# Page11_PMIC_PCA9450B.net
KiCad netlist of a schematic drawn in Altium Designer
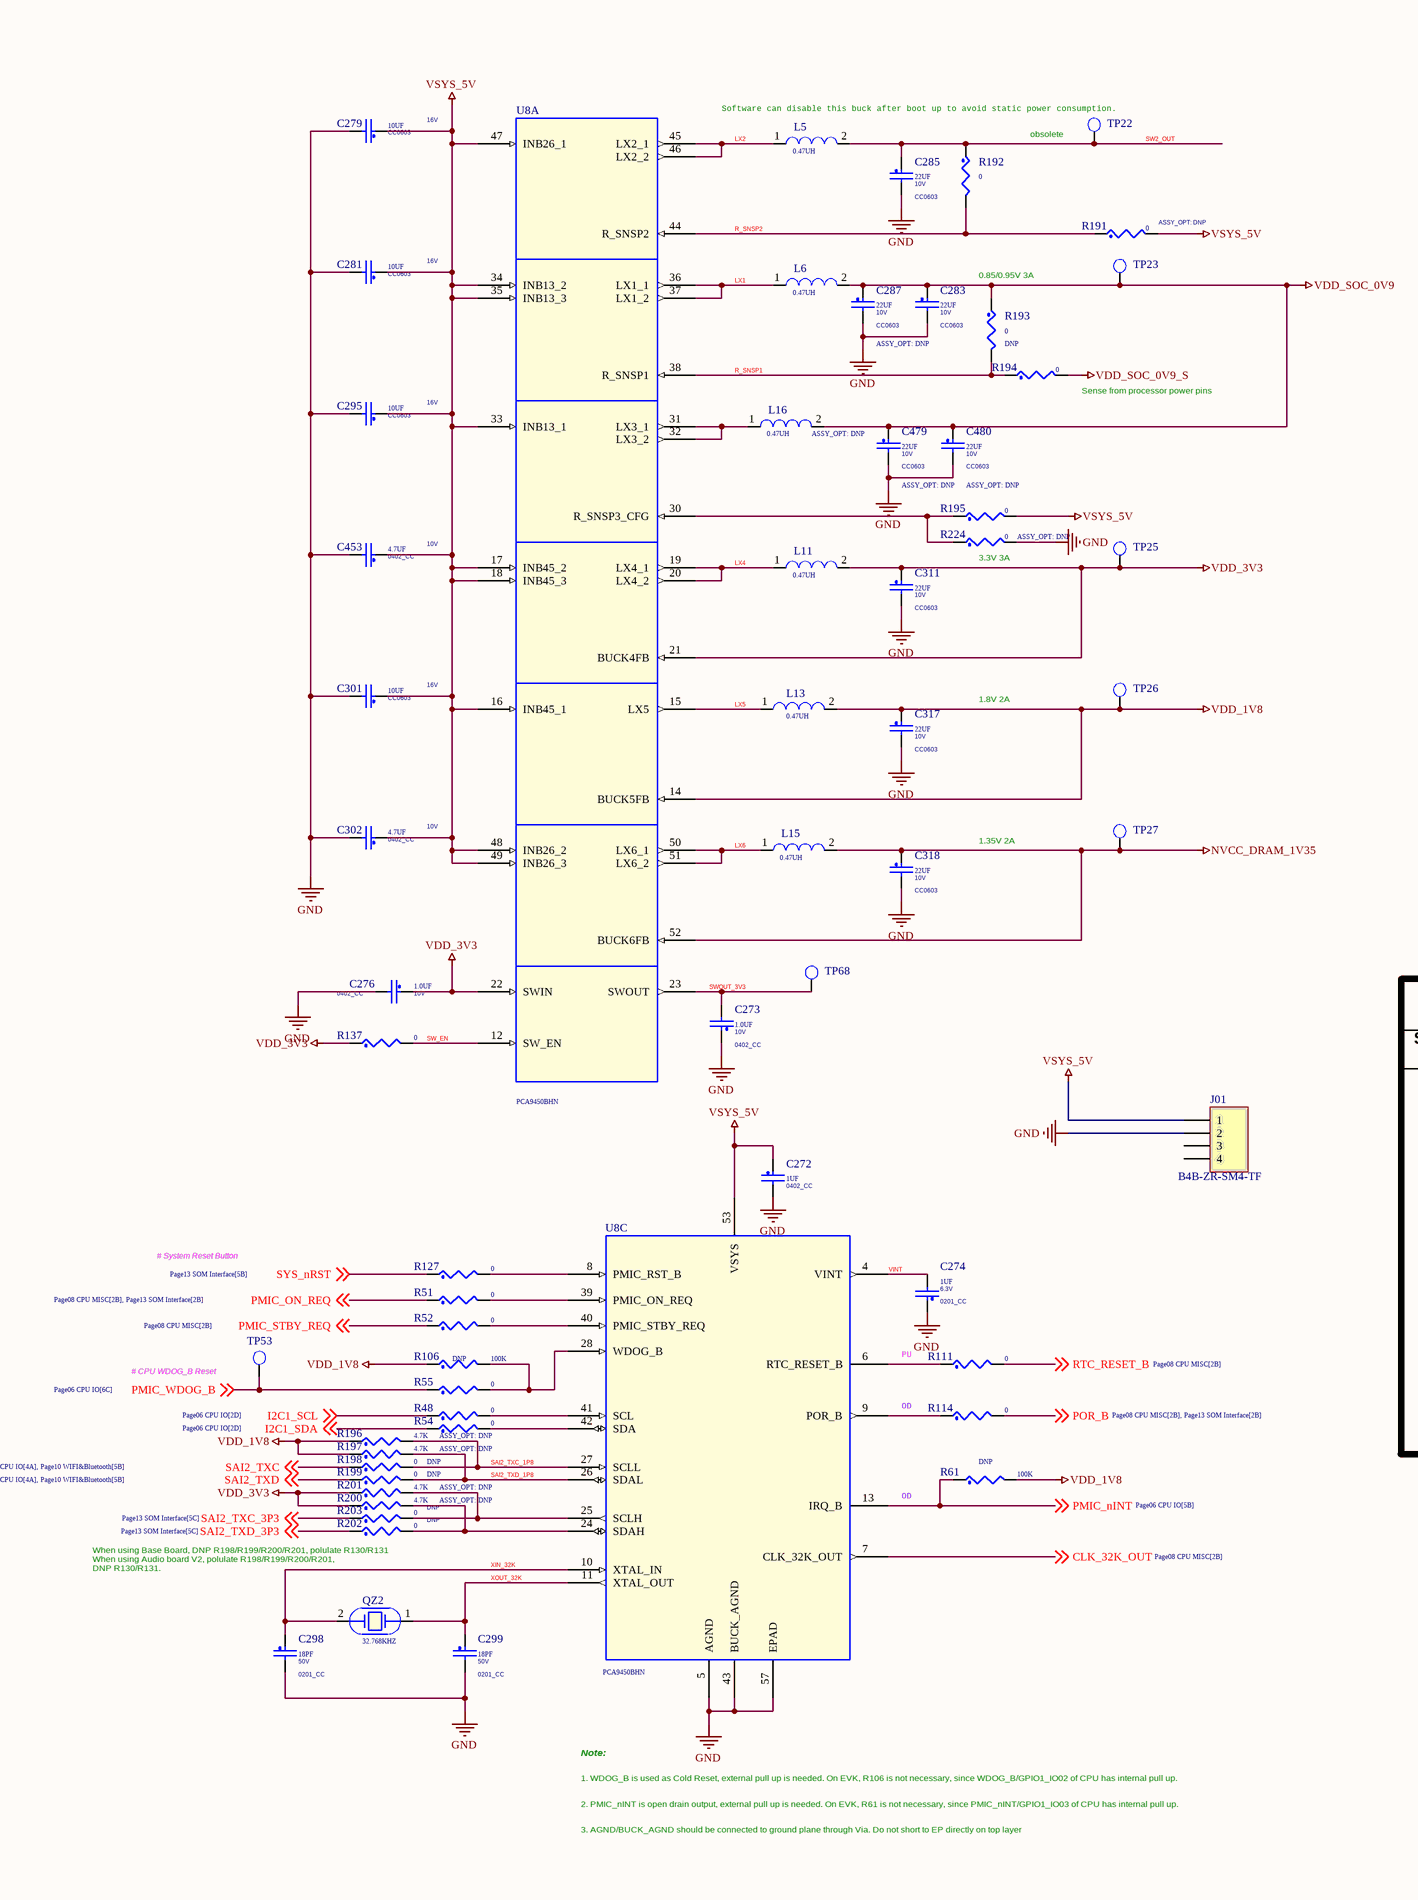
[diagram p0: Page11 PMIC PCA9450B.SchDoc, left]
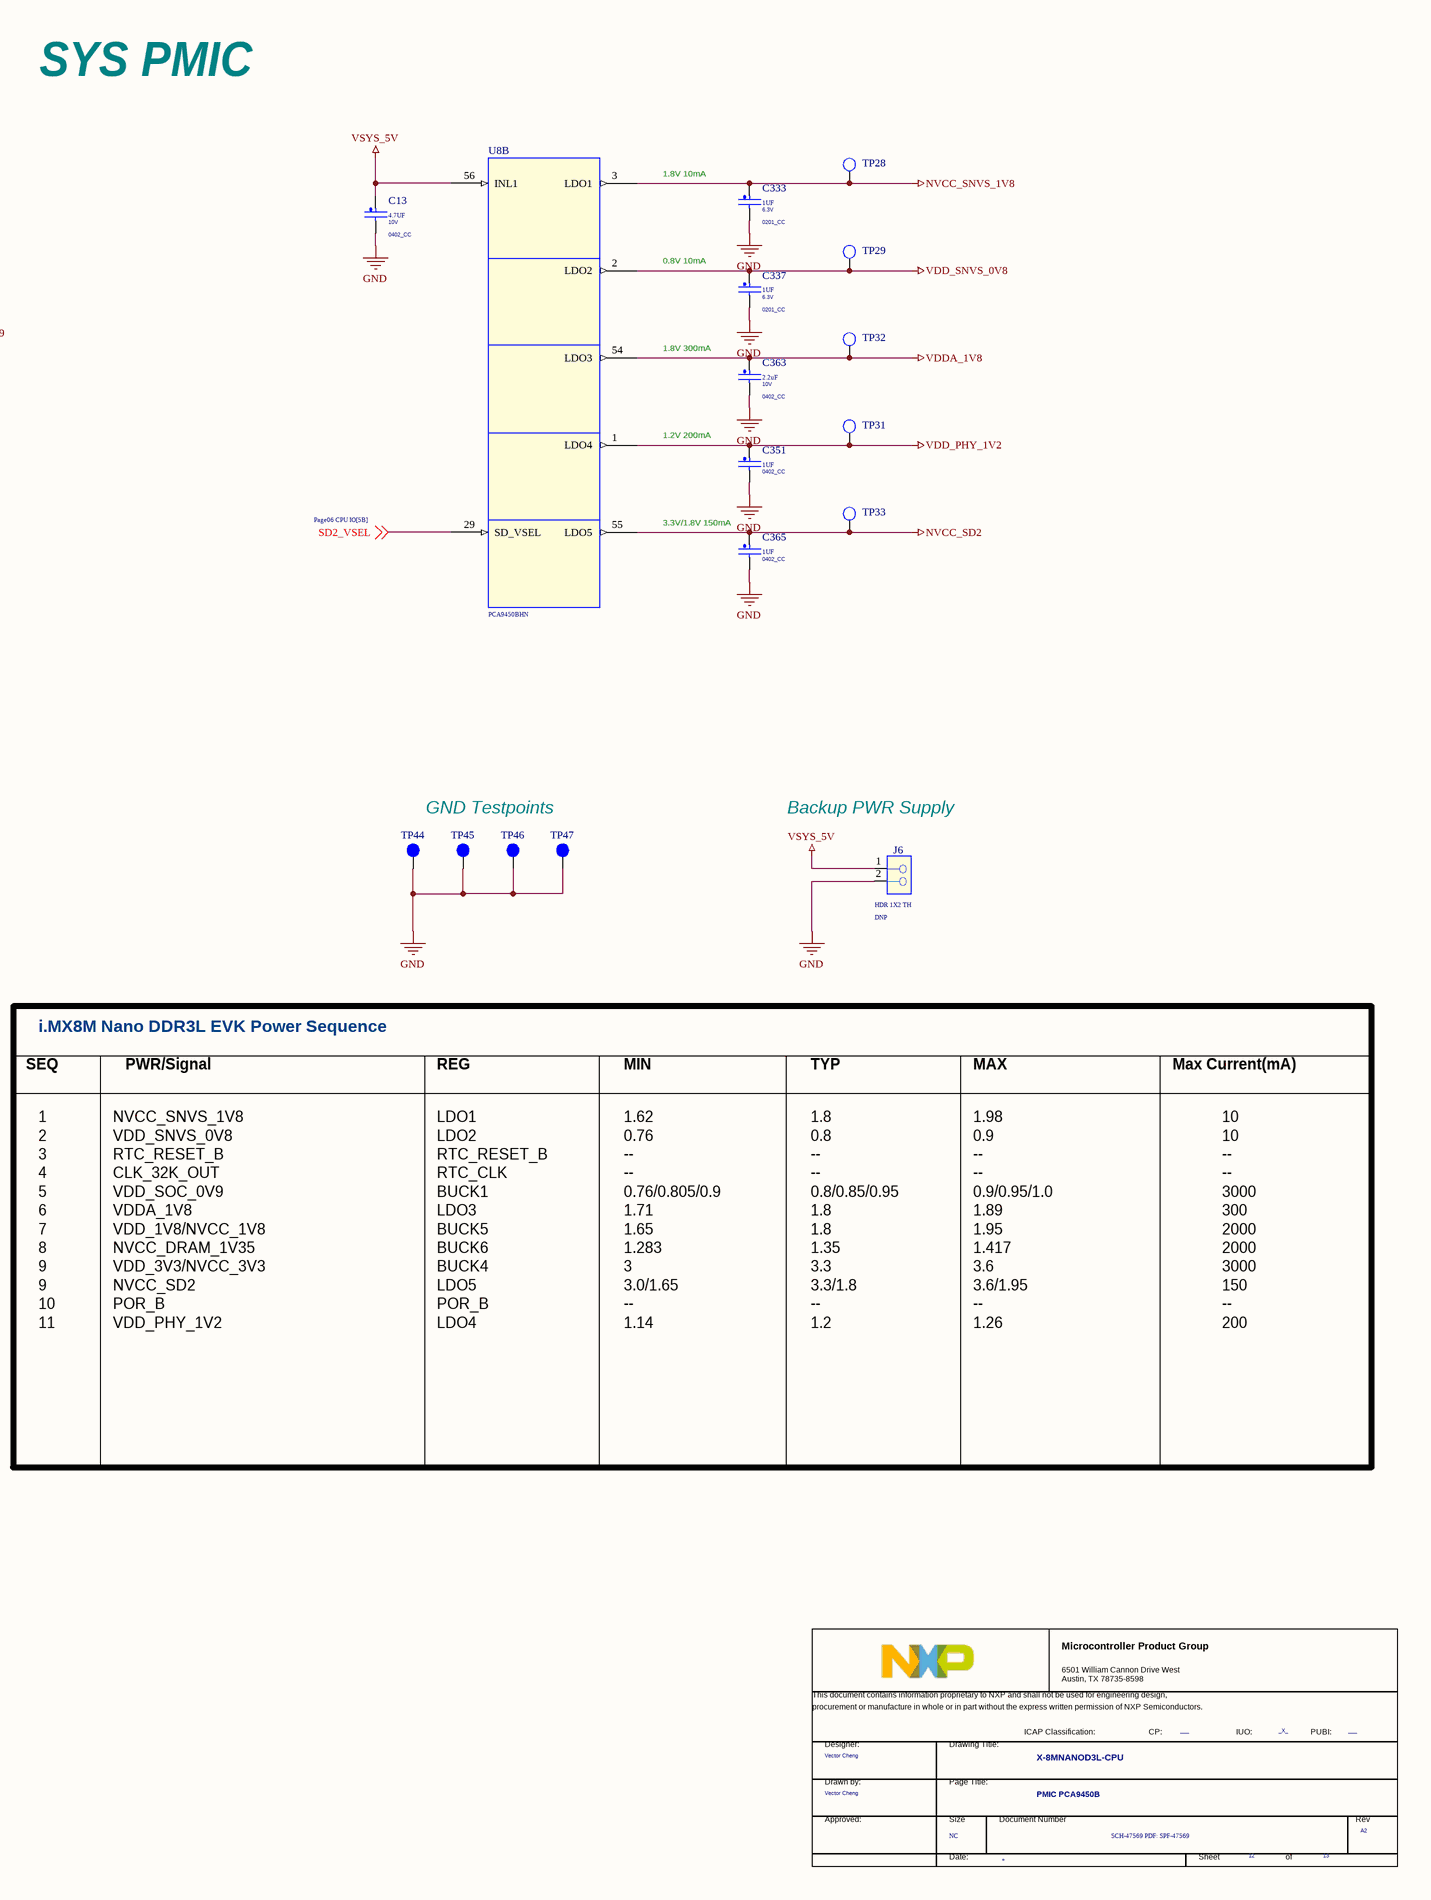
[diagram p1: Page11 PMIC PCA9450B.SchDoc, right]

(export (version "E")
  (design (tool "Eeschema 10.0.6"))
  (components
    (comp (ref "C13")
      (value "4.7UF")
      (footprint "0402_CC - C")
      (description "CAP CER 4.7uF 10V 10% X5R 0402")
      (fields
        (field (name "VOLTAGE") "10V")
        (field (name "TOLERANCE") "10%")
        (field (name "PCB FOOTPRINT") "0402_CC")
      )
      (libsource (lib "*") (part "CAP_NP"))
    )
    (comp (ref "C272")
      (value "1UF")
      (footprint "0402_CC - C")
      (description "CAP CER 1uF 10V 10% X7S 0402")
      (fields
        (field (name "VOLTAGE") "10")
        (field (name "TOLERANCE") "10%")
        (field (name "PCB FOOTPRINT") "0402_CC")
      )
      (libsource (lib "*") (part "CAP_NP"))
    )
    (comp (ref "C273")
      (value "1.0UF")
      (footprint "0402_CC - C")
      (description "CAP CER 1.0UF 10V 10% X5R 0402")
      (fields (field (name "PCB FOOTPRINT") "0402_CC") (field (name "VOLTAGE") "10V"))
      (libsource (lib "*") (part "CAP_NP"))
    )
    (comp (ref "C274")
      (value "1UF")
      (footprint "0201_CC - C")
      (description "CAP CER 1uF 6.3V 20% X5R 0201")
      (fields
        (field (name "TOLERANCE") "20%")
        (field (name "VOLTAGE") "6.3V")
        (field (name "PCB FOOTPRINT") "0201_CC")
      )
      (libsource (lib "*") (part "CAP_NP"))
    )
    (comp (ref "C276")
      (value "1.0UF")
      (footprint "0402_CC - C")
      (description "CAP CER 1.0UF 10V 10% X5R 0402")
      (fields (field (name "PCB FOOTPRINT") "0402_CC") (field (name "VOLTAGE") "10V"))
      (libsource (lib "*") (part "CAP_NP"))
    )
    (comp (ref "C279")
      (value "10UF")
      (footprint "0603_CC")
      (description "CAP CER 10.0uF 16V 10% X5R 0603")
      (fields
        (field (name "VOLTAGE") "16V")
        (field (name "TOLERANCE") "10%")
        (field (name "PCB FOOTPRINT") "CC0603")
      )
      (libsource (lib "*") (part "CAP_NP"))
    )
    (comp (ref "C281")
      (value "10UF")
      (footprint "0603_CC")
      (description "CAP CER 10.0uF 16V 10% X5R 0603")
      (fields
        (field (name "VOLTAGE") "16V")
        (field (name "TOLERANCE") "10%")
        (field (name "PCB FOOTPRINT") "CC0603")
      )
      (libsource (lib "*") (part "CAP_NP"))
    )
    (comp (ref "C283")
      (value "22UF")
      (footprint "0603_CC")
      (description "CAP CER 22uF 10V 20% X5R 0603")
      (fields
        (field (name "VOLTAGE") "10V")
        (field (name "TOLERANCE") "20%")
        (field (name "PCB FOOTPRINT") "CC0603")
      )
      (libsource (lib "*") (part "CAP_NP"))
    )
    (comp (ref "C285")
      (value "22UF")
      (footprint "0603_CC")
      (description "CAP CER 22uF 10V 20% X5R 0603")
      (fields
        (field (name "PCB FOOTPRINT") "CC0603")
        (field (name "VOLTAGE") "10V")
        (field (name "TOLERANCE") "20%")
      )
      (libsource (lib "*") (part "CAP_NP"))
    )
    (comp (ref "C287")
      (value "22UF")
      (footprint "0603_CC")
      (description "CAP CER 22uF 10V 20% X5R 0603")
      (fields
        (field (name "ASSY_OPT") "DNP")
        (field (name "VOLTAGE") "10V")
        (field (name "TOLERANCE") "20%")
        (field (name "PCB FOOTPRINT") "CC0603")
      )
      (libsource (lib "*") (part "CAP_NP"))
    )
    (comp (ref "C295")
      (value "10UF")
      (footprint "0603_CC")
      (description "CAP CER 10.0uF 16V 10% X5R 0603")
      (fields
        (field (name "TOLERANCE") "10%")
        (field (name "VOLTAGE") "16V")
        (field (name "PCB FOOTPRINT") "CC0603")
      )
      (libsource (lib "*") (part "CAP_NP"))
    )
    (comp (ref "C298")
      (value "18PF")
      (footprint "0201_CC - C")
      (description "CAP CER 18pF 50V 5% C0G 0201")
      (fields
        (field (name "VOLTAGE") "50V")
        (field (name "TOLERANCE") "5%")
        (field (name "PCB FOOTPRINT") "0201_CC")
      )
      (libsource (lib "*") (part "CAP_NP"))
    )
    (comp (ref "C299")
      (value "18PF")
      (footprint "0201_CC - C")
      (description "CAP CER 18pF 50V 5% C0G 0201")
      (fields
        (field (name "TOLERANCE") "5%")
        (field (name "VOLTAGE") "50V")
        (field (name "PCB FOOTPRINT") "0201_CC")
      )
      (libsource (lib "*") (part "CAP_NP"))
    )
    (comp (ref "C301")
      (value "10UF")
      (footprint "0603_CC")
      (description "CAP CER 10.0uF 16V 10% X5R 0603")
      (fields
        (field (name "TOLERANCE") "10%")
        (field (name "VOLTAGE") "16V")
        (field (name "PCB FOOTPRINT") "CC0603")
      )
      (libsource (lib "*") (part "CAP_NP"))
    )
    (comp (ref "C302")
      (value "4.7UF")
      (footprint "0402_CC - C")
      (description "CAP CER 4.7uF 10V 10% X5R 0402")
      (fields
        (field (name "PCB FOOTPRINT") "0402_CC")
        (field (name "TOLERANCE") "10%")
        (field (name "VOLTAGE") "10V")
      )
      (libsource (lib "*") (part "CAP_NP"))
    )
    (comp (ref "C311")
      (value "22UF")
      (footprint "0603_CC")
      (description "CAP CER 22uF 10V 20% X5R 0603")
      (fields
        (field (name "VOLTAGE") "10V")
        (field (name "TOLERANCE") "20%")
        (field (name "PCB FOOTPRINT") "CC0603")
      )
      (libsource (lib "*") (part "CAP_NP"))
    )
    (comp (ref "C317")
      (value "22UF")
      (footprint "0603_CC")
      (description "CAP CER 22uF 10V 20% X5R 0603")
      (fields
        (field (name "VOLTAGE") "10V")
        (field (name "TOLERANCE") "20%")
        (field (name "PCB FOOTPRINT") "CC0603")
      )
      (libsource (lib "*") (part "CAP_NP"))
    )
    (comp (ref "C318")
      (value "22UF")
      (footprint "0603_CC")
      (description "CAP CER 22uF 10V 20% X5R 0603")
      (fields
        (field (name "VOLTAGE") "10V")
        (field (name "TOLERANCE") "20%")
        (field (name "PCB FOOTPRINT") "CC0603")
      )
      (libsource (lib "*") (part "CAP_NP"))
    )
    (comp (ref "C333")
      (value "1UF")
      (footprint "0201_CC - C")
      (description "CAP CER 1uF 6.3V 20% X5R 0201")
      (fields
        (field (name "VOLTAGE") "6.3V")
        (field (name "TOLERANCE") "20%")
        (field (name "PCB FOOTPRINT") "0201_CC")
      )
      (libsource (lib "*") (part "CAP_NP"))
    )
    (comp (ref "C337")
      (value "1UF")
      (footprint "0201_CC - C")
      (description "CAP CER 1uF 6.3V 20% X5R 0201")
      (fields
        (field (name "VOLTAGE") "6.3V")
        (field (name "TOLERANCE") "20%")
        (field (name "PCB FOOTPRINT") "0201_CC")
      )
      (libsource (lib "*") (part "CAP_NP"))
    )
    (comp (ref "C351")
      (value "1UF")
      (footprint "0402_CC - C")
      (description "CAP CER 1uF 10V 10% X7S 0402")
      (fields
        (field (name "TOLERANCE") "10%")
        (field (name "VOLTAGE") "10")
        (field (name "PCB FOOTPRINT") "0402_CC")
      )
      (libsource (lib "*") (part "CAP_NP"))
    )
    (comp (ref "C363")
      (value "2.2uF")
      (footprint "0402_CC - C")
      (description "CAP CER 2.2uF 10V 10% X5R 0402")
      (fields
        (field (name "TOLERANCE") "10%")
        (field (name "VOLTAGE") "10V")
        (field (name "PCB FOOTPRINT") "0402_CC")
      )
      (libsource (lib "*") (part "CAP_NP"))
    )
    (comp (ref "C365")
      (value "1UF")
      (footprint "0402_CC - C")
      (description "CAP CER 1uF 10V 10% X7S 0402")
      (fields
        (field (name "VOLTAGE") "10")
        (field (name "TOLERANCE") "10%")
        (field (name "PCB FOOTPRINT") "0402_CC")
      )
      (libsource (lib "*") (part "CAP_NP"))
    )
    (comp (ref "C453")
      (value "4.7UF")
      (footprint "0402_CC - C")
      (description "CAP CER 4.7uF 10V 10% X5R 0402")
      (fields
        (field (name "PCB FOOTPRINT") "0402_CC")
        (field (name "VOLTAGE") "10V")
        (field (name "TOLERANCE") "10%")
      )
      (libsource (lib "*") (part "CAP_NP"))
    )
    (comp (ref "C479")
      (value "22UF")
      (footprint "0603_CC")
      (description "CAP CER 22uF 10V 20% X5R 0603")
      (fields
        (field (name "ASSY_OPT") "DNP")
        (field (name "TOLERANCE") "20%")
        (field (name "VOLTAGE") "10V")
        (field (name "PCB FOOTPRINT") "CC0603")
      )
      (libsource (lib "*") (part "CAP_NP"))
    )
    (comp (ref "C480")
      (value "22UF")
      (footprint "0603_CC")
      (description "CAP CER 22uF 10V 20% X5R 0603")
      (fields
        (field (name "ASSY_OPT") "DNP")
        (field (name "TOLERANCE") "20%")
        (field (name "VOLTAGE") "10V")
        (field (name "PCB FOOTPRINT") "CC0603")
      )
      (libsource (lib "*") (part "CAP_NP"))
    )
    (comp (ref "J01")
      (value "B4B-ZR-SM4-TF")
      (footprint "JST_B4B-ZR-SM4-TFT(LF)(SN)")
      (fields (field (name "PUBLISHER") "Altium Limited"))
      (libsource (lib "Miscellaneous Connectors") (part "Header 4"))
    )
    (comp (ref "J6")
      (value "HDR 1X2 TH")
      (footprint "HDR_1X2")
      (description "HDR 1X2 TH 100MIL SP 339H AU 98L")
      (fields (field (name "ASSY_OPT") "DNP"))
      (libsource (lib "*") (part "CONN_HDR_2X1"))
    )
    (comp (ref "L5")
      (value "0.47UH")
      (footprint "ind_sph2520")
      (description "IND PWR 0.47uH@1MHZ 4.7A 20% SMT")
      (fields (field (name "TOLERANCE") "20%"))
      (libsource (lib "*") (part "INDUCTOR"))
    )
    (comp (ref "L6")
      (value "0.47UH")
      (footprint "ind_sph2520")
      (description "IND PWR 0.47uH@1MHZ 4.7A 20% SMT")
      (fields (field (name "TOLERANCE") "20%"))
      (libsource (lib "*") (part "INDUCTOR"))
    )
    (comp (ref "L11")
      (value "0.47UH")
      (footprint "ind_sph2520")
      (description "IND PWR 0.47uH@1MHZ 4.7A 20% SMT")
      (fields (field (name "TOLERANCE") "20%"))
      (libsource (lib "*") (part "INDUCTOR"))
    )
    (comp (ref "L13")
      (value "0.47UH")
      (footprint "IND_SPH2520")
      (description "IND WW 0.47uH@1MHz 3.4A 20% 2016")
      (fields (field (name "TOLERANCE") "20%") (field (name "VOLTAGE") "20V DC"))
      (libsource (lib "*") (part "INDUCTOR"))
    )
    (comp (ref "L15")
      (value "0.47UH")
      (footprint "ind_sph2520")
      (description "IND PWR 0.47uH@1MHZ 4.7A 20% SMT")
      (fields (field (name "TOLERANCE") "20%"))
      (libsource (lib "*") (part "INDUCTOR"))
    )
    (comp (ref "L16")
      (value "0.47UH")
      (footprint "ind_sph2520")
      (description "IND PWR 0.47uH@1MHZ 4.7A 20% SMT")
      (fields (field (name "ASSY_OPT") "DNP") (field (name "TOLERANCE") "20%"))
      (libsource (lib "*") (part "INDUCTOR"))
    )
    (comp (ref "QZ2")
      (value "32.768KHZ")
      (footprint "XTAL_ABS07-32.768KHZ-T - duplicate")
      (description "XTAL 32.768KHZ 12.5PF 20PPM 3.2X1.5MM SMT")
      (libsource (lib "*") (part "XTAL"))
    )
    (comp (ref "R48")
      (value "0")
      (footprint "0402_CC_RES")
      (description "RES MF ZERO OHM 1/16W 5% 0402")
      (fields (field (name "TOLERANCE") "5%") (field (name "VOLTAGE") "1/16W"))
      (libsource (lib "*") (part "RES"))
    )
    (comp (ref "R51")
      (value "0")
      (footprint "0402_CC_RES")
      (description "RES MF ZERO OHM 1/16W 5% 0402")
      (fields (field (name "TOLERANCE") "5%") (field (name "VOLTAGE") "1/16W"))
      (libsource (lib "*") (part "RES"))
    )
    (comp (ref "R52")
      (value "0")
      (footprint "0402_CC_RES")
      (description "RES MF ZERO OHM 1/16W 5% 0402")
      (fields (field (name "TOLERANCE") "5%") (field (name "VOLTAGE") "1/16W"))
      (libsource (lib "*") (part "RES"))
    )
    (comp (ref "R54")
      (value "0")
      (footprint "0402_CC_RES")
      (description "RES MF ZERO OHM 1/16W 5% 0402")
      (fields (field (name "TOLERANCE") "5%") (field (name "VOLTAGE") "1/16W"))
      (libsource (lib "*") (part "RES"))
    )
    (comp (ref "R55")
      (value "0")
      (footprint "0402_CC_RES")
      (description "RES MF ZERO OHM 1/16W 5% 0402")
      (fields (field (name "VOLTAGE") "1/16W") (field (name "TOLERANCE") "5%"))
      (libsource (lib "*") (part "RES"))
    )
    (comp (ref "R61")
      (value "100K")
      (footprint "0201_RES")
      (description "RES MF 100K 1/20W 1% 0201")
      (fields (field (name "ASSY_OPT") "DNP") (field (name "TOLERANCE") "1%"))
      (libsource (lib "*") (part "RES"))
    )
    (comp (ref "R106")
      (value "100K")
      (footprint "0201_RES")
      (description "RES MF 100K 1/20W 1% 0201")
      (fields (field (name "ASSY_OPT") "DNP") (field (name "TOLERANCE") "1%"))
      (libsource (lib "*") (part "RES"))
    )
    (comp (ref "R111")
      (value "0")
      (footprint "0402_CC_RES")
      (description "RES MF ZERO OHM 1/16W 5% 0402")
      (fields (field (name "TOLERANCE") "5%") (field (name "VOLTAGE") "1/16W"))
      (libsource (lib "*") (part "RES"))
    )
    (comp (ref "R114")
      (value "0")
      (footprint "0402_CC_RES")
      (description "RES MF ZERO OHM 1/16W 5% 0402")
      (fields (field (name "TOLERANCE") "5%") (field (name "VOLTAGE") "1/16W"))
      (libsource (lib "*") (part "RES"))
    )
    (comp (ref "R127")
      (value "0")
      (footprint "0402_CC_RES")
      (description "RES MF ZERO OHM 1/16W 5% 0402")
      (fields (field (name "VOLTAGE") "1/16W") (field (name "TOLERANCE") "5%"))
      (libsource (lib "*") (part "RES"))
    )
    (comp (ref "R137")
      (value "0")
      (footprint "0402_CC_RES")
      (description "RES MF ZERO OHM 1/16W 5% 0402")
      (fields (field (name "TOLERANCE") "5%") (field (name "VOLTAGE") "1/16W"))
      (libsource (lib "*") (part "RES"))
    )
    (comp (ref "R191")
      (value "0")
      (footprint "0402_CC_RES")
      (description "RES MF ZERO OHM 1/16W 5% 0402")
      (fields
        (field (name "ASSY_OPT") "DNP")
        (field (name "TOLERANCE") "5%")
        (field (name "VOLTAGE") "1/16W")
      )
      (libsource (lib "*") (part "RES"))
    )
    (comp (ref "R192")
      (value "0")
      (footprint "0402_CC_RES")
      (description "RES MF ZERO OHM 1/16W 5% 0402")
      (fields (field (name "TOLERANCE") "5%") (field (name "VOLTAGE") "1/16W"))
      (libsource (lib "*") (part "RES"))
    )
    (comp (ref "R193")
      (value "0")
      (footprint "0402_CC_RES")
      (description "RES MF ZERO OHM 1/16W 5% 0402")
      (fields
        (field (name "ASSY_OPT") "DNP")
        (field (name "TOLERANCE") "5%")
        (field (name "VOLTAGE") "1/16W")
      )
      (libsource (lib "*") (part "RES"))
    )
    (comp (ref "R194")
      (value "0")
      (footprint "0402_CC_RES")
      (description "RES MF ZERO OHM 1/16W 5% 0402")
      (fields (field (name "TOLERANCE") "5%") (field (name "VOLTAGE") "1/16W"))
      (libsource (lib "*") (part "RES"))
    )
    (comp (ref "R195")
      (value "0")
      (footprint "0402_CC_RES")
      (description "RES MF ZERO OHM 1/16W 5% 0402")
      (fields (field (name "TOLERANCE") "5%") (field (name "VOLTAGE") "1/16W"))
      (libsource (lib "*") (part "RES"))
    )
    (comp (ref "R196")
      (value "4.7K")
      (footprint "0201_RES")
      (description "RES MF 4.7K 1/20W 5% AEC-Q200 0201")
      (fields (field (name "ASSY_OPT") "DNP") (field (name "TOLERANCE") "5%"))
      (libsource (lib "*") (part "RES"))
    )
    (comp (ref "R197")
      (value "4.7K")
      (footprint "0201_RES")
      (description "RES MF 4.7K 1/20W 5% AEC-Q200 0201")
      (fields (field (name "ASSY_OPT") "DNP") (field (name "TOLERANCE") "5%"))
      (libsource (lib "*") (part "RES"))
    )
    (comp (ref "R198")
      (value "0")
      (footprint "0402_CC_RES")
      (description "RES MF ZERO OHM 1/16W 5% 0402")
      (fields
        (field (name "ASSY_OPT") "DNP")
        (field (name "TOLERANCE") "5%")
        (field (name "VOLTAGE") "1/16W")
      )
      (libsource (lib "*") (part "RES"))
    )
    (comp (ref "R199")
      (value "0")
      (footprint "0402_CC_RES")
      (description "RES MF ZERO OHM 1/16W 5% 0402")
      (fields
        (field (name "ASSY_OPT") "DNP")
        (field (name "TOLERANCE") "5%")
        (field (name "VOLTAGE") "1/16W")
      )
      (libsource (lib "*") (part "RES"))
    )
    (comp (ref "R200")
      (value "4.7K")
      (footprint "0201_RES")
      (description "RES MF 4.7K 1/20W 5% AEC-Q200 0201")
      (fields (field (name "ASSY_OPT") "DNP") (field (name "TOLERANCE") "5%"))
      (libsource (lib "*") (part "RES"))
    )
    (comp (ref "R201")
      (value "4.7K")
      (footprint "0201_RES")
      (description "RES MF 4.7K 1/20W 5% AEC-Q200 0201")
      (fields (field (name "ASSY_OPT") "DNP") (field (name "TOLERANCE") "5%"))
      (libsource (lib "*") (part "RES"))
    )
    (comp (ref "R202")
      (value "0")
      (footprint "0402_CC_RES")
      (description "RES MF ZERO OHM 1/16W 5% 0402")
      (fields
        (field (name "ASSY_OPT") "DNP")
        (field (name "TOLERANCE") "5%")
        (field (name "VOLTAGE") "1/16W")
      )
      (libsource (lib "*") (part "RES"))
    )
    (comp (ref "R203")
      (value "0")
      (footprint "0402_CC_RES")
      (description "RES MF ZERO OHM 1/16W 5% 0402")
      (fields
        (field (name "ASSY_OPT") "DNP")
        (field (name "TOLERANCE") "5%")
        (field (name "VOLTAGE") "1/16W")
      )
      (libsource (lib "*") (part "RES"))
    )
    (comp (ref "R224")
      (value "0")
      (footprint "0402_CC_RES")
      (description "RES MF ZERO OHM 1/16W 5% 0402")
      (fields
        (field (name "ASSY_OPT") "DNP")
        (field (name "TOLERANCE") "5%")
        (field (name "VOLTAGE") "1/16W")
      )
      (libsource (lib "*") (part "RES"))
    )
    (comp (ref "TP22")
      (value "TP_35MIL")
      (footprint "Test Pin")
      (description "TEST POINT PAD .035 SMT, no part to order")
      (libsource (lib "*") (part "T POINT R"))
    )
    (comp (ref "TP23")
      (value "TP_35MIL")
      (footprint "Test Pin")
      (description "TEST POINT PAD .035 SMT, no part to order")
      (libsource (lib "*") (part "T POINT R"))
    )
    (comp (ref "TP25")
      (value "TP_35MIL")
      (footprint "Test Pin")
      (description "TEST POINT PAD .035 SMT, no part to order")
      (libsource (lib "*") (part "T POINT R"))
    )
    (comp (ref "TP26")
      (value "TP_35MIL")
      (footprint "Test Pin")
      (description "TEST POINT PAD .035 SMT, no part to order")
      (libsource (lib "*") (part "T POINT R"))
    )
    (comp (ref "TP27")
      (value "TP_35MIL")
      (footprint "Test Pin")
      (description "TEST POINT PAD .035 SMT, no part to order")
      (libsource (lib "*") (part "T POINT R"))
    )
    (comp (ref "TP28")
      (value "TP_35MIL")
      (footprint "Test Pin")
      (description "TEST POINT PAD .035 SMT, no part to order")
      (libsource (lib "*") (part "T POINT R"))
    )
    (comp (ref "TP29")
      (value "TP_35MIL")
      (footprint "Test Pin")
      (description "TEST POINT PAD .035 SMT, no part to order")
      (libsource (lib "*") (part "T POINT R"))
    )
    (comp (ref "TP31")
      (value "TP_35MIL")
      (footprint "Test Pin")
      (description "TEST POINT PAD .035 SMT, no part to order")
      (libsource (lib "*") (part "T POINT R"))
    )
    (comp (ref "TP32")
      (value "TP_35MIL")
      (footprint "Test Pin")
      (description "TEST POINT PAD .035 SMT, no part to order")
      (libsource (lib "*") (part "T POINT R"))
    )
    (comp (ref "TP33")
      (value "TP_35MIL")
      (footprint "Test Pin")
      (description "TEST POINT PAD .035 SMT, no part to order")
      (libsource (lib "*") (part "T POINT R"))
    )
    (comp (ref "TP44")
      (value "TPAD_050")
      (footprint "Test Pin")
      (description "TEST POINT PAD 50MIL DIA SMT, NO PART TO ORDER")
      (libsource (lib "*") (part "TESTLOOP"))
    )
    (comp (ref "TP45")
      (value "TPAD_050")
      (footprint "Test Pin")
      (description "TEST POINT PAD 50MIL DIA SMT, NO PART TO ORDER")
      (libsource (lib "*") (part "TESTLOOP"))
    )
    (comp (ref "TP46")
      (value "TPAD_050")
      (footprint "Test Pin")
      (description "TEST POINT PAD 50MIL DIA SMT, NO PART TO ORDER")
      (libsource (lib "*") (part "TESTLOOP"))
    )
    (comp (ref "TP47")
      (value "TPAD_050")
      (footprint "Test Pin")
      (description "TEST POINT PAD 50MIL DIA SMT, NO PART TO ORDER")
      (libsource (lib "*") (part "TESTLOOP"))
    )
    (comp (ref "TP53")
      (value "TP_35MIL")
      (footprint "Test Pin")
      (description "TEST POINT PAD .035 SMT, no part to order")
      (libsource (lib "*") (part "T POINT R"))
    )
    (comp (ref "TP68")
      (value "TP_35MIL")
      (footprint "Test Pin")
      (description "TEST POINT PAD .035 SMT, no part to order")
      (libsource (lib "*") (part "T POINT R"))
    )
    (comp (ref "U8")
      (value "PCA9450BHN")
      (footprint "QFN40P700X700X100-57N-D")
      (description "IC POWER MANAGEMENT 2.7-5.5V HVQFN56")
      (fields (field (name "VOLTAGE") "2.7-5.5V"))
      (libsource (lib "*") (part "PCA9450_HVQFN56P_A"))
    )
  )
  (nets
    (net (code "1") (name "/LX1") (class "Default")
      (node (ref "L6") (pin "1") (pinfunction "1_1") (pintype "passive"))
      (node (ref "U8") (pin "36") (pinfunction "LX1_1_36") (pintype "output"))
      (node (ref "U8") (pin "37") (pinfunction "LX1_2_37") (pintype "output"))
    )
    (net (code "2") (name "/LX2") (class "Default")
      (node (ref "L5") (pin "1") (pinfunction "1_1") (pintype "passive"))
      (node (ref "U8") (pin "45") (pinfunction "LX2_1_45") (pintype "output"))
      (node (ref "U8") (pin "46") (pinfunction "LX2_2_46") (pintype "output"))
    )
    (net (code "3") (name "/LX4") (class "Default")
      (node (ref "L11") (pin "1") (pinfunction "1_1") (pintype "passive"))
      (node (ref "U8") (pin "19") (pinfunction "LX4_1_19") (pintype "output"))
      (node (ref "U8") (pin "20") (pinfunction "LX4_2_20") (pintype "output"))
    )
    (net (code "4") (name "/LX5") (class "Default")
      (node (ref "L13") (pin "1") (pinfunction "1_1") (pintype "passive"))
      (node (ref "U8") (pin "15") (pinfunction "LX5_15") (pintype "output"))
    )
    (net (code "5") (name "/LX6") (class "Default")
      (node (ref "L15") (pin "1") (pinfunction "1_1") (pintype "passive"))
      (node (ref "U8") (pin "50") (pinfunction "LX6_1_50") (pintype "output"))
      (node (ref "U8") (pin "51") (pinfunction "LX6_2_51") (pintype "output"))
    )
    (net (code "6") (name "/R_SNSP1") (class "Default")
      (node (ref "R193") (pin "2") (pinfunction "2_2") (pintype "passive"))
      (node (ref "R194") (pin "1") (pinfunction "1_1") (pintype "passive"))
      (node (ref "U8") (pin "38") (pinfunction "R_SNSP1_38") (pintype "input"))
    )
    (net (code "7") (name "/R_SNSP2") (class "Default")
      (node (ref "R191") (pin "1") (pinfunction "1_1") (pintype "passive"))
      (node (ref "R192") (pin "2") (pinfunction "2_2") (pintype "passive"))
      (node (ref "U8") (pin "44") (pinfunction "R_SNSP2_44") (pintype "input"))
    )
    (net (code "8") (name "/SAI2_TXC_1P8") (class "Default")
      (node (ref "R196") (pin "2") (pinfunction "2_2") (pintype "passive"))
      (node (ref "R198") (pin "2") (pinfunction "2_2") (pintype "passive"))
      (node (ref "U8") (pin "27") (pinfunction "SCLL_27") (pintype "input"))
    )
    (net (code "9") (name "/SAI2_TXD_1P8") (class "Default")
      (node (ref "R197") (pin "2") (pinfunction "2_2") (pintype "passive"))
      (node (ref "R199") (pin "2") (pinfunction "2_2") (pintype "passive"))
      (node (ref "U8") (pin "26") (pinfunction "SDAL_26") (pintype "bidirectional"))
    )
    (net (code "10") (name "/SW2_OUT") (class "Default")
      (node (ref "C285") (pin "1") (pinfunction "1_1") (pintype "passive"))
      (node (ref "L5") (pin "2") (pinfunction "2_2") (pintype "passive"))
      (node (ref "R192") (pin "1") (pinfunction "1_1") (pintype "passive"))
      (node (ref "TP22") (pin "1") (pinfunction "TP_1") (pintype "passive"))
    )
    (net (code "11") (name "/SWOUT_3V3") (class "Default")
      (node (ref "C273") (pin "2") (pinfunction "2_2") (pintype "passive"))
      (node (ref "TP68") (pin "1") (pinfunction "TP_1") (pintype "passive"))
      (node (ref "U8") (pin "23") (pinfunction "SWOUT_23") (pintype "output"))
    )
    (net (code "12") (name "/SW_EN") (class "Default")
      (node (ref "R137") (pin "2") (pinfunction "2_2") (pintype "passive"))
      (node (ref "U8") (pin "12") (pinfunction "SW_EN_12") (pintype "input"))
    )
    (net (code "13") (name "/VINT") (class "Default")
      (node (ref "C274") (pin "2") (pinfunction "2_2") (pintype "passive"))
      (node (ref "U8") (pin "4") (pinfunction "VINT_4") (pintype "output"))
    )
    (net (code "14") (name "/XIN_32K") (class "Default")
      (node (ref "C298") (pin "1") (pinfunction "1_1") (pintype "passive"))
      (node (ref "QZ2") (pin "2") (pinfunction "2_2") (pintype "passive"))
      (node (ref "U8") (pin "10") (pinfunction "XTAL_IN_10") (pintype "input"))
    )
    (net (code "15") (name "/XOUT_32K") (class "Default")
      (node (ref "C299") (pin "1") (pinfunction "1_1") (pintype "passive"))
      (node (ref "QZ2") (pin "1") (pinfunction "1_1") (pintype "passive"))
      (node (ref "U8") (pin "11") (pinfunction "XTAL_OUT_11") (pintype "output"))
    )
    (net (code "16") (name "CLK_32K_OUT") (class "Default")
      (node (ref "U8") (pin "7") (pinfunction "CLK_32K_OUT_7") (pintype "output"))
    )
    (net (code "17") (name "GND") (class "Default")
      (node (ref "C13") (pin "2") (pinfunction "2_2") (pintype "passive"))
      (node (ref "C272") (pin "2") (pinfunction "2_2") (pintype "passive"))
      (node (ref "C273") (pin "1") (pinfunction "1_1") (pintype "passive"))
      (node (ref "C274") (pin "1") (pinfunction "1_1") (pintype "passive"))
      (node (ref "C276") (pin "2") (pinfunction "2_2") (pintype "passive"))
      (node (ref "C279") (pin "2") (pinfunction "2_2") (pintype "passive"))
      (node (ref "C281") (pin "2") (pinfunction "2_2") (pintype "passive"))
      (node (ref "C283") (pin "2") (pinfunction "2_2") (pintype "passive"))
      (node (ref "C285") (pin "2") (pinfunction "2_2") (pintype "passive"))
      (node (ref "C287") (pin "2") (pinfunction "2_2") (pintype "passive"))
      (node (ref "C295") (pin "2") (pinfunction "2_2") (pintype "passive"))
      (node (ref "C298") (pin "2") (pinfunction "2_2") (pintype "passive"))
      (node (ref "C299") (pin "2") (pinfunction "2_2") (pintype "passive"))
      (node (ref "C301") (pin "2") (pinfunction "2_2") (pintype "passive"))
      (node (ref "C302") (pin "2") (pinfunction "2_2") (pintype "passive"))
      (node (ref "C311") (pin "2") (pinfunction "2_2") (pintype "passive"))
      (node (ref "C317") (pin "2") (pinfunction "2_2") (pintype "passive"))
      (node (ref "C318") (pin "2") (pinfunction "2_2") (pintype "passive"))
      (node (ref "C333") (pin "2") (pinfunction "2_2") (pintype "passive"))
      (node (ref "C337") (pin "2") (pinfunction "2_2") (pintype "passive"))
      (node (ref "C351") (pin "2") (pinfunction "2_2") (pintype "passive"))
      (node (ref "C363") (pin "2") (pinfunction "2_2") (pintype "passive"))
      (node (ref "C365") (pin "2") (pinfunction "2_2") (pintype "passive"))
      (node (ref "C453") (pin "2") (pinfunction "2_2") (pintype "passive"))
      (node (ref "C479") (pin "2") (pinfunction "2_2") (pintype "passive"))
      (node (ref "C480") (pin "2") (pinfunction "2_2") (pintype "passive"))
      (node (ref "J01") (pin "2") (pinfunction "2_2") (pintype "passive"))
      (node (ref "J6") (pin "2") (pinfunction "2_2") (pintype "passive"))
      (node (ref "R224") (pin "2") (pinfunction "2_2") (pintype "passive"))
      (node (ref "TP44") (pin "1") (pinfunction "Pin1_1") (pintype "passive"))
      (node (ref "TP45") (pin "1") (pinfunction "Pin1_1") (pintype "passive"))
      (node (ref "TP46") (pin "1") (pinfunction "Pin1_1") (pintype "passive"))
      (node (ref "TP47") (pin "1") (pinfunction "Pin1_1") (pintype "passive"))
      (node (ref "U8") (pin "43") (pinfunction "BUCK_AGND_43") (pintype "power_in"))
      (node (ref "U8") (pin "5") (pinfunction "AGND_5") (pintype "power_in"))
      (node (ref "U8") (pin "57") (pinfunction "EPAD_57") (pintype "power_in"))
    )
    (net (code "18") (name "I2C1_SCL") (class "Default")
      (node (ref "R48") (pin "1") (pinfunction "1_1") (pintype "passive"))
    )
    (net (code "19") (name "I2C1_SDA") (class "Default")
      (node (ref "R54") (pin "1") (pinfunction "1_1") (pintype "passive"))
    )
    (net (code "20") (name "NVCC_DRAM_1V35") (class "Default")
      (node (ref "C318") (pin "1") (pinfunction "1_1") (pintype "passive"))
      (node (ref "L15") (pin "2") (pinfunction "2_2") (pintype "passive"))
      (node (ref "TP27") (pin "1") (pinfunction "TP_1") (pintype "passive"))
      (node (ref "U8") (pin "52") (pinfunction "BUCK6FB_52") (pintype "input"))
    )
    (net (code "21") (name "NVCC_SD2") (class "Default")
      (node (ref "C365") (pin "1") (pinfunction "1_1") (pintype "passive"))
      (node (ref "TP33") (pin "1") (pinfunction "TP_1") (pintype "passive"))
      (node (ref "U8") (pin "55") (pinfunction "LDO5_55") (pintype "output"))
    )
    (net (code "22") (name "NVCC_SNVS_1V8") (class "Default")
      (node (ref "C333") (pin "1") (pinfunction "1_1") (pintype "passive"))
      (node (ref "TP28") (pin "1") (pinfunction "TP_1") (pintype "passive"))
      (node (ref "U8") (pin "3") (pinfunction "LDO1_3") (pintype "output"))
    )
    (net (code "23") (name "Net-(U8A-LX3_1)") (class "Default")
      (node (ref "L16") (pin "1") (pinfunction "1_1") (pintype "passive"))
      (node (ref "U8") (pin "31") (pinfunction "LX3_1_31") (pintype "output"))
      (node (ref "U8") (pin "32") (pinfunction "LX3_2_32") (pintype "output"))
    )
    (net (code "24") (name "Net-(U8A-R_SNSP3_CFG)") (class "Default")
      (node (ref "R195") (pin "1") (pinfunction "1_1") (pintype "passive"))
      (node (ref "R224") (pin "1") (pinfunction "1_1") (pintype "passive"))
      (node (ref "U8") (pin "30") (pinfunction "R_SNSP3_CFG_30") (pintype "input"))
    )
    (net (code "25") (name "Net-(U8C-PMIC_ON_REQ)") (class "Default")
      (node (ref "R51") (pin "2") (pinfunction "2_2") (pintype "passive"))
      (node (ref "U8") (pin "39") (pinfunction "PMIC_ON_REQ_39") (pintype "input"))
    )
    (net (code "26") (name "Net-(U8C-PMIC_RST_B)") (class "Default")
      (node (ref "R127") (pin "2") (pinfunction "2_2") (pintype "passive"))
      (node (ref "U8") (pin "8") (pinfunction "PMIC_RST_B_8") (pintype "input"))
    )
    (net (code "27") (name "Net-(U8C-PMIC_STBY_REQ)") (class "Default")
      (node (ref "R52") (pin "2") (pinfunction "2_2") (pintype "passive"))
      (node (ref "U8") (pin "40") (pinfunction "PMIC_STBY_REQ_40") (pintype "input"))
    )
    (net (code "28") (name "Net-(U8C-POR_B)") (class "Default")
      (node (ref "R114") (pin "1") (pinfunction "1_1") (pintype "passive"))
      (node (ref "U8") (pin "9") (pinfunction "POR_B_9") (pintype "output"))
    )
    (net (code "29") (name "Net-(U8C-RTC_RESET_B)") (class "Default")
      (node (ref "R111") (pin "1") (pinfunction "1_1") (pintype "passive"))
      (node (ref "U8") (pin "6") (pinfunction "RTC_RESET_B_6") (pintype "open_collector"))
    )
    (net (code "30") (name "Net-(U8C-SCL)") (class "Default")
      (node (ref "R48") (pin "2") (pinfunction "2_2") (pintype "passive"))
      (node (ref "U8") (pin "41") (pinfunction "SCL_41") (pintype "input"))
    )
    (net (code "31") (name "Net-(U8C-SCLH)") (class "Default")
      (node (ref "R201") (pin "2") (pinfunction "2_2") (pintype "passive"))
      (node (ref "R203") (pin "2") (pinfunction "2_2") (pintype "passive"))
      (node (ref "U8") (pin "25") (pinfunction "SCLH_25") (pintype "output"))
    )
    (net (code "32") (name "Net-(U8C-SDA)") (class "Default")
      (node (ref "R54") (pin "2") (pinfunction "2_2") (pintype "passive"))
      (node (ref "U8") (pin "42") (pinfunction "SDA_42") (pintype "bidirectional"))
    )
    (net (code "33") (name "Net-(U8C-SDAH)") (class "Default")
      (node (ref "R200") (pin "2") (pinfunction "2_2") (pintype "passive"))
      (node (ref "R202") (pin "2") (pinfunction "2_2") (pintype "passive"))
      (node (ref "U8") (pin "24") (pinfunction "SDAH_24") (pintype "bidirectional"))
    )
    (net (code "34") (name "Net-(U8C-WDOG_B)") (class "Default")
      (node (ref "R106") (pin "2") (pinfunction "2_2") (pintype "passive"))
      (node (ref "R55") (pin "2") (pinfunction "2_2") (pintype "passive"))
      (node (ref "U8") (pin "28") (pinfunction "WDOG_B_28") (pintype "input"))
    )
    (net (code "35") (name "PMIC_ON_REQ") (class "Default")
      (node (ref "R51") (pin "1") (pinfunction "1_1") (pintype "passive"))
    )
    (net (code "36") (name "PMIC_STBY_REQ") (class "Default")
      (node (ref "R52") (pin "1") (pinfunction "1_1") (pintype "passive"))
    )
    (net (code "37") (name "PMIC_WDOG_B") (class "Default")
      (node (ref "R55") (pin "1") (pinfunction "1_1") (pintype "passive"))
      (node (ref "TP53") (pin "1") (pinfunction "TP_1") (pintype "passive"))
    )
    (net (code "38") (name "PMIC_nINT") (class "Default")
      (node (ref "R61") (pin "1") (pinfunction "1_1") (pintype "passive"))
      (node (ref "U8") (pin "13") (pinfunction "IRQ_B_13") (pintype "open_collector"))
    )
    (net (code "39") (name "POR_B") (class "Default")
      (node (ref "R114") (pin "2") (pinfunction "2_2") (pintype "passive"))
    )
    (net (code "40") (name "RTC_RESET_B") (class "Default")
      (node (ref "R111") (pin "2") (pinfunction "2_2") (pintype "passive"))
    )
    (net (code "41") (name "SAI2_TXC") (class "Default")
      (node (ref "R198") (pin "1") (pinfunction "1_1") (pintype "passive"))
    )
    (net (code "42") (name "SAI2_TXC_3P3") (class "Default")
      (node (ref "R203") (pin "1") (pinfunction "1_1") (pintype "passive"))
    )
    (net (code "43") (name "SAI2_TXD") (class "Default")
      (node (ref "R199") (pin "1") (pinfunction "1_1") (pintype "passive"))
    )
    (net (code "44") (name "SAI2_TXD_3P3") (class "Default")
      (node (ref "R202") (pin "1") (pinfunction "1_1") (pintype "passive"))
    )
    (net (code "45") (name "SD2_VSEL") (class "Default")
      (node (ref "U8") (pin "29") (pinfunction "SD_VSEL_29") (pintype "input"))
    )
    (net (code "46") (name "SYS_nRST") (class "Default")
      (node (ref "R127") (pin "1") (pinfunction "1_1") (pintype "passive"))
    )
    (net (code "47") (name "VDDA_1V8") (class "Default")
      (node (ref "C363") (pin "1") (pinfunction "1_1") (pintype "passive"))
      (node (ref "TP32") (pin "1") (pinfunction "TP_1") (pintype "passive"))
      (node (ref "U8") (pin "54") (pinfunction "LDO3_54") (pintype "output"))
    )
    (net (code "48") (name "VDD_1V8") (class "Default")
      (node (ref "C317") (pin "1") (pinfunction "1_1") (pintype "passive"))
      (node (ref "L13") (pin "2") (pinfunction "2_2") (pintype "passive"))
      (node (ref "R106") (pin "1") (pinfunction "1_1") (pintype "passive"))
      (node (ref "R196") (pin "1") (pinfunction "1_1") (pintype "passive"))
      (node (ref "R197") (pin "1") (pinfunction "1_1") (pintype "passive"))
      (node (ref "R61") (pin "2") (pinfunction "2_2") (pintype "passive"))
      (node (ref "TP26") (pin "1") (pinfunction "TP_1") (pintype "passive"))
      (node (ref "U8") (pin "14") (pinfunction "BUCK5FB_14") (pintype "input"))
    )
    (net (code "49") (name "VDD_3V3") (class "Default")
      (node (ref "C276") (pin "1") (pinfunction "1_1") (pintype "passive"))
      (node (ref "C311") (pin "1") (pinfunction "1_1") (pintype "passive"))
      (node (ref "L11") (pin "2") (pinfunction "2_2") (pintype "passive"))
      (node (ref "R137") (pin "1") (pinfunction "1_1") (pintype "passive"))
      (node (ref "R200") (pin "1") (pinfunction "1_1") (pintype "passive"))
      (node (ref "R201") (pin "1") (pinfunction "1_1") (pintype "passive"))
      (node (ref "TP25") (pin "1") (pinfunction "TP_1") (pintype "passive"))
      (node (ref "U8") (pin "21") (pinfunction "BUCK4FB_21") (pintype "input"))
      (node (ref "U8") (pin "22") (pinfunction "SWIN_22") (pintype "input"))
    )
    (net (code "50") (name "VDD_PHY_1V2") (class "Default")
      (node (ref "C351") (pin "1") (pinfunction "1_1") (pintype "passive"))
      (node (ref "TP31") (pin "1") (pinfunction "TP_1") (pintype "passive"))
      (node (ref "U8") (pin "1") (pinfunction "LDO4_1") (pintype "output"))
    )
    (net (code "51") (name "VDD_SNVS_0V8") (class "Default")
      (node (ref "C337") (pin "1") (pinfunction "1_1") (pintype "passive"))
      (node (ref "TP29") (pin "1") (pinfunction "TP_1") (pintype "passive"))
      (node (ref "U8") (pin "2") (pinfunction "LDO2_2") (pintype "output"))
    )
    (net (code "52") (name "VDD_SOC_0V9") (class "Default")
      (node (ref "C283") (pin "1") (pinfunction "1_1") (pintype "passive"))
      (node (ref "C287") (pin "1") (pinfunction "1_1") (pintype "passive"))
      (node (ref "C479") (pin "1") (pinfunction "1_1") (pintype "passive"))
      (node (ref "C480") (pin "1") (pinfunction "1_1") (pintype "passive"))
      (node (ref "L16") (pin "2") (pinfunction "2_2") (pintype "passive"))
      (node (ref "L6") (pin "2") (pinfunction "2_2") (pintype "passive"))
      (node (ref "R193") (pin "1") (pinfunction "1_1") (pintype "passive"))
      (node (ref "TP23") (pin "1") (pinfunction "TP_1") (pintype "passive"))
    )
    (net (code "53") (name "VDD_SOC_0V9_S") (class "Default")
      (node (ref "R194") (pin "2") (pinfunction "2_2") (pintype "passive"))
    )
    (net (code "54") (name "VSYS_5V") (class "Default")
      (node (ref "C13") (pin "1") (pinfunction "1_1") (pintype "passive"))
      (node (ref "C272") (pin "1") (pinfunction "1_1") (pintype "passive"))
      (node (ref "C279") (pin "1") (pinfunction "1_1") (pintype "passive"))
      (node (ref "C281") (pin "1") (pinfunction "1_1") (pintype "passive"))
      (node (ref "C295") (pin "1") (pinfunction "1_1") (pintype "passive"))
      (node (ref "C301") (pin "1") (pinfunction "1_1") (pintype "passive"))
      (node (ref "C302") (pin "1") (pinfunction "1_1") (pintype "passive"))
      (node (ref "C453") (pin "1") (pinfunction "1_1") (pintype "passive"))
      (node (ref "J01") (pin "1") (pinfunction "1_1") (pintype "passive"))
      (node (ref "J6") (pin "1") (pinfunction "1_1") (pintype "passive"))
      (node (ref "R191") (pin "2") (pinfunction "2_2") (pintype "passive"))
      (node (ref "R195") (pin "2") (pinfunction "2_2") (pintype "passive"))
      (node (ref "U8") (pin "16") (pinfunction "INB45_1_16") (pintype "input"))
      (node (ref "U8") (pin "17") (pinfunction "INB45_2_17") (pintype "input"))
      (node (ref "U8") (pin "18") (pinfunction "INB45_3_18") (pintype "input"))
      (node (ref "U8") (pin "33") (pinfunction "INB13_1_33") (pintype "input"))
      (node (ref "U8") (pin "34") (pinfunction "INB13_2_34") (pintype "input"))
      (node (ref "U8") (pin "35") (pinfunction "INB13_3_35") (pintype "input"))
      (node (ref "U8") (pin "47") (pinfunction "INB26_1_47") (pintype "input"))
      (node (ref "U8") (pin "48") (pinfunction "INB26_2_48") (pintype "input"))
      (node (ref "U8") (pin "49") (pinfunction "INB26_3_49") (pintype "input"))
      (node (ref "U8") (pin "53") (pinfunction "VSYS_53") (pintype "power_in"))
      (node (ref "U8") (pin "56") (pinfunction "INL1_56") (pintype "input"))
    )
    (net (code "55") (name "unconnected-(J01-Pad3)") (class "Default")
      (node (ref "J01") (pin "3") (pinfunction "3_3") (pintype "passive"))
    )
    (net (code "56") (name "unconnected-(J01-Pad4)") (class "Default")
      (node (ref "J01") (pin "4") (pinfunction "4_4") (pintype "passive"))
    )
  )
)
